# buslamp-r4.net
KiCad netlist of a schematic drawn in EAGLE
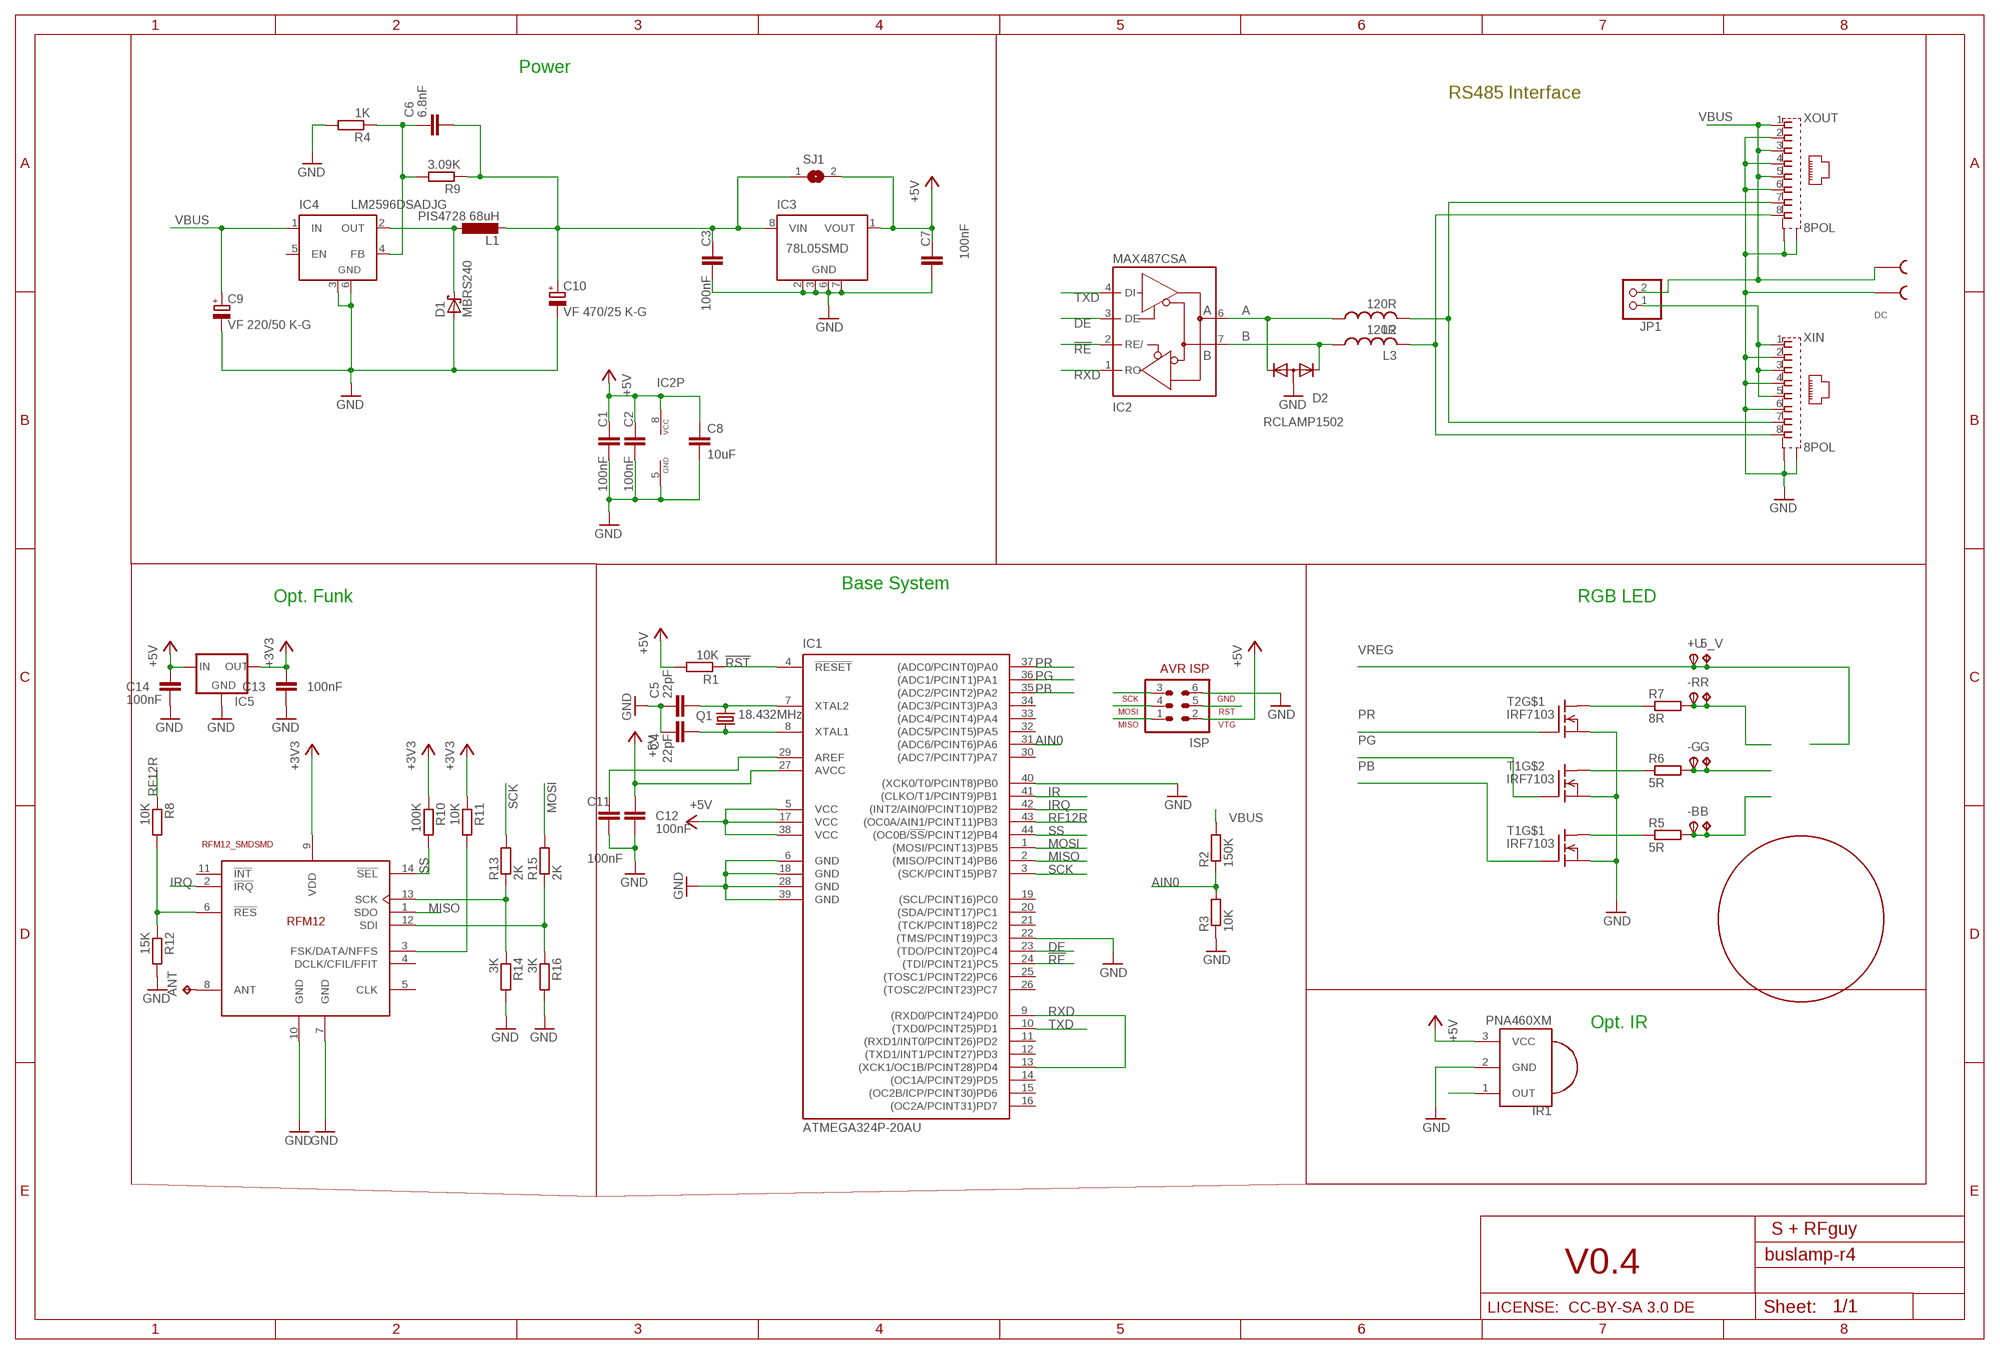
[diagram p0: schematic, sheet 1]

(export (version "E")
  (design (tool "Eeschema 10.0.6"))
  (components
    (comp (ref "+U")
      (value "TPSTP212R")
      (footprint "eagle-import:TP212R")
      (libsource (lib "eagle-import") (part "TPSTP212R"))
    )
    (comp (ref "-B")
      (value "TPSTP212R")
      (footprint "eagle-import:TP212R")
      (libsource (lib "eagle-import") (part "TPSTP212R"))
    )
    (comp (ref "-G")
      (value "TPSTP212R")
      (footprint "eagle-import:TP212R")
      (libsource (lib "eagle-import") (part "TPSTP212R"))
    )
    (comp (ref "-R")
      (value "TPSTP212R")
      (footprint "eagle-import:TP212R")
      (libsource (lib "eagle-import") (part "TPSTP212R"))
    )
    (comp (ref "5_V")
      (value "TPPAD1-13")
      (footprint "eagle-import:P1-13")
      (libsource (lib "eagle-import") (part "TPPAD1-13"))
    )
    (comp (ref "ANT")
      (value "TPPAD1-13")
      (footprint "eagle-import:P1-13")
      (libsource (lib "eagle-import") (part "TPPAD1-13"))
    )
    (comp (ref "B")
      (value "TPPAD1-13")
      (footprint "eagle-import:P1-13")
      (libsource (lib "eagle-import") (part "TPPAD1-13"))
    )
    (comp (ref "C1")
      (value "100nF")
      (footprint "eagle-import:C0805K")
      (libsource (lib "eagle-import") (part "C-EUC0805K"))
    )
    (comp (ref "C2")
      (value "100nF")
      (footprint "eagle-import:C0805K")
      (libsource (lib "eagle-import") (part "C-EUC0805K"))
    )
    (comp (ref "C3")
      (value "100nF")
      (footprint "eagle-import:C0805K")
      (libsource (lib "eagle-import") (part "C-EUC0805K"))
    )
    (comp (ref "C4")
      (value "22pF")
      (footprint "eagle-import:C0805K")
      (libsource (lib "eagle-import") (part "C-EUC0805K"))
    )
    (comp (ref "C5")
      (value "22pF")
      (footprint "eagle-import:C0805K")
      (libsource (lib "eagle-import") (part "C-EUC0805K"))
    )
    (comp (ref "C6")
      (value "6.8nF")
      (footprint "eagle-import:C0805K")
      (libsource (lib "eagle-import") (part "C-EUC0805K"))
    )
    (comp (ref "C7")
      (value "100nF")
      (footprint "eagle-import:C0805K")
      (libsource (lib "eagle-import") (part "C-EUC0805K"))
    )
    (comp (ref "C8")
      (value "10uF")
      (footprint "eagle-import:C1210")
      (libsource (lib "eagle-import") (part "C-EUC1210"))
    )
    (comp (ref "C9")
      (value "VF 220/50 K-G")
      (footprint "eagle-import:UD-10X10_NICHICON")
      (libsource (lib "eagle-import") (part "CPOL-EUUD-10X10"))
    )
    (comp (ref "C10")
      (value "VF 470/25 K-G")
      (footprint "eagle-import:UD-10X10_NICHICON")
      (libsource (lib "eagle-import") (part "CPOL-EUUD-10X10"))
    )
    (comp (ref "C11")
      (value "100nF")
      (footprint "eagle-import:C0805")
      (libsource (lib "eagle-import") (part "C-EUC0805"))
    )
    (comp (ref "C12")
      (value "100nF")
      (footprint "eagle-import:C0805")
      (libsource (lib "eagle-import") (part "C-EUC0805"))
    )
    (comp (ref "C13")
      (value "100nF")
      (footprint "eagle-import:C0805")
      (libsource (lib "eagle-import") (part "C-EUC0805"))
    )
    (comp (ref "C14")
      (value "100nF")
      (footprint "eagle-import:C0805")
      (libsource (lib "eagle-import") (part "C-EUC0805"))
    )
    (comp (ref "D1")
      (value "MBRS240")
      (footprint "eagle-import:SMB")
      (libsource (lib "eagle-import") (part "MBRS130LT3"))
    )
    (comp (ref "D2")
      (value "RCLAMP1502")
      (footprint "eagle-import:SOT23")
      (libsource (lib "eagle-import") (part "DIODE-2CA|ACSOT23"))
    )
    (comp (ref "DC")
      (value "STL-266-2")
      (footprint "eagle-import:STL-266-2")
      (libsource (lib "eagle-import") (part "STL-266-2"))
    )
    (comp (ref "G")
      (value "TPPAD1-13")
      (footprint "eagle-import:P1-13")
      (libsource (lib "eagle-import") (part "TPPAD1-13"))
    )
    (comp (ref "IC1")
      (value "ATMEGA324P-20AU")
      (footprint "eagle-import:TQFP44")
      (libsource (lib "eagle-import") (part "MEGA164P/324P/644P-AU"))
    )
    (comp (ref "IC2")
      (value "MAX487CSA")
      (footprint "eagle-import:SO08")
      (libsource (lib "eagle-import") (part "MAX481CSA"))
    )
    (comp (ref "IC3")
      (value "78L05SMD")
      (footprint "eagle-import:SO08")
      (libsource (lib "eagle-import") (part "78LSMD05"))
    )
    (comp (ref "IC4")
      (value "LM2596DSADJG")
      (footprint "eagle-import:TO263-5")
      (libsource (lib "eagle-import") (part "LM2596S"))
    )
    (comp (ref "IC5")
      (value "MCP1700SOT23")
      (footprint "eagle-import:SOT23")
      (libsource (lib "eagle-import") (part "MCP1700SOT23"))
    )
    (comp (ref "IR1")
      (value "PNA460XM")
      (footprint "eagle-import:PNA460XM")
      (libsource (lib "eagle-import") (part "PNA460XM"))
    )
    (comp (ref "ISP")
      (value "AVR-ISP-6")
      (footprint "eagle-import:AVR-ISP-6")
      (libsource (lib "eagle-import") (part "AVR-ISP-6"))
    )
    (comp (ref "JP1")
      (value "PINHD-1X2")
      (footprint "eagle-import:1X02")
      (libsource (lib "eagle-import") (part "PINHD-1X2"))
    )
    (comp (ref "L1")
      (value "PIS4728 68uH")
      (footprint "eagle-import:PIS4728")
      (libsource (lib "eagle-import") (part "PSI4728"))
    )
    (comp (ref "L2")
      (value "120R")
      (footprint "eagle-import:L0603")
      (libsource (lib "eagle-import") (part "L-USL0603"))
    )
    (comp (ref "L3")
      (value "120R")
      (footprint "eagle-import:L0603")
      (libsource (lib "eagle-import") (part "L-USL0603"))
    )
    (comp (ref "Q1")
      (value "18.432MHz")
      (footprint "eagle-import:HC49_S")
      (libsource (lib "eagle-import") (part "CRYTALHC49S"))
    )
    (comp (ref "R")
      (value "TPPAD1-13")
      (footprint "eagle-import:P1-13")
      (libsource (lib "eagle-import") (part "TPPAD1-13"))
    )
    (comp (ref "R1")
      (value "10K")
      (footprint "eagle-import:M0805")
      (libsource (lib "eagle-import") (part "R-EU_M0805"))
    )
    (comp (ref "R2")
      (value "150K")
      (footprint "eagle-import:R0805")
      (libsource (lib "eagle-import") (part "R-EU_R0805"))
    )
    (comp (ref "R3")
      (value "10K")
      (footprint "eagle-import:R0805")
      (libsource (lib "eagle-import") (part "R-EU_R0805"))
    )
    (comp (ref "R4")
      (value "1K")
      (footprint "eagle-import:M0805")
      (libsource (lib "eagle-import") (part "R-EU_M0805"))
    )
    (comp (ref "R5")
      (value "5R")
      (footprint "eagle-import:0617_17")
      (libsource (lib "eagle-import") (part "rclml_R-EU_0617/17"))
    )
    (comp (ref "R6")
      (value "5R")
      (footprint "eagle-import:0617_17")
      (libsource (lib "eagle-import") (part "rclml_R-EU_0617/17"))
    )
    (comp (ref "R7")
      (value "8R")
      (footprint "eagle-import:0617_17")
      (libsource (lib "eagle-import") (part "rclml_R-EU_0617/17"))
    )
    (comp (ref "R8")
      (value "10K")
      (footprint "eagle-import:M0805")
      (libsource (lib "eagle-import") (part "R-EU_M0805"))
    )
    (comp (ref "R9")
      (value "3.09K")
      (footprint "eagle-import:M0805")
      (libsource (lib "eagle-import") (part "R-EU_M0805"))
    )
    (comp (ref "R10")
      (value "100K")
      (footprint "eagle-import:M0805")
      (libsource (lib "eagle-import") (part "R-EU_M0805"))
    )
    (comp (ref "R11")
      (value "10K")
      (footprint "eagle-import:M0805")
      (libsource (lib "eagle-import") (part "R-EU_M0805"))
    )
    (comp (ref "R12")
      (value "15K")
      (footprint "eagle-import:M0805")
      (libsource (lib "eagle-import") (part "R-EU_M0805"))
    )
    (comp (ref "R13")
      (value "2K")
      (footprint "eagle-import:M0805")
      (libsource (lib "eagle-import") (part "R-EU_M0805"))
    )
    (comp (ref "R14")
      (value "3K")
      (footprint "eagle-import:M0805")
      (libsource (lib "eagle-import") (part "R-EU_M0805"))
    )
    (comp (ref "R15")
      (value "2K")
      (footprint "eagle-import:M0805")
      (libsource (lib "eagle-import") (part "R-EU_M0805"))
    )
    (comp (ref "R16")
      (value "3K")
      (footprint "eagle-import:M0805")
      (libsource (lib "eagle-import") (part "R-EU_M0805"))
    )
    (comp (ref "RF1")
      (value "RFM12_SMDSMD")
      (footprint "eagle-import:RFM12")
      (libsource (lib "eagle-import") (part "RFM12_SMDSMD"))
    )
    (comp (ref "SJ1") (value "SJ") (footprint "eagle-import:SJ") (libsource (lib "eagle-import") (part "SJ")))
    (comp (ref "T1")
      (value "IRF7103")
      (footprint "eagle-import:SO-8")
      (libsource (lib "eagle-import") (part "IRF7103"))
    )
    (comp (ref "T2")
      (value "IRF7103")
      (footprint "eagle-import:SO-8")
      (libsource (lib "eagle-import") (part "IRF7103"))
    )
    (comp (ref "U$2")
      (value "KK-STERN")
      (footprint "eagle-import:STERN")
      (libsource (lib "eagle-import") (part "KK-STERN"))
    )
    (comp (ref "XIN")
      (value "8POL")
      (footprint "eagle-import:8POL")
      (libsource (lib "eagle-import") (part "8POL"))
    )
    (comp (ref "XOUT")
      (value "8POL")
      (footprint "eagle-import:8POL")
      (libsource (lib "eagle-import") (part "8POL"))
    )
  )
  (nets
    (net (code "1") (name "+3V3") (class "Default")
      (node (ref "C13") (pin "2") (pinfunction "2_2") (pintype "passive"))
      (node (ref "IC5") (pin "2") (pinfunction "OUT_2") (pintype "passive"))
      (node (ref "R10") (pin "1") (pinfunction "1_1") (pintype "passive"))
      (node (ref "R11") (pin "1") (pinfunction "1_1") (pintype "passive"))
      (node (ref "RF1") (pin "9") (pinfunction "VDD_9") (pintype "power_in"))
    )
    (net (code "2") (name "+5V") (class "Default")
      (node (ref "C1") (pin "1") (pinfunction "1_1") (pintype "passive"))
      (node (ref "C12") (pin "2") (pinfunction "2_2") (pintype "passive"))
      (node (ref "C14") (pin "2") (pinfunction "2_2") (pintype "passive"))
      (node (ref "C2") (pin "1") (pinfunction "1_1") (pintype "passive"))
      (node (ref "C7") (pin "1") (pinfunction "1_1") (pintype "passive"))
      (node (ref "C8") (pin "1") (pinfunction "1_1") (pintype "passive"))
      (node (ref "IC1") (pin "17") (pinfunction "VCC_17") (pintype "power_in"))
      (node (ref "IC1") (pin "27") (pinfunction "AVCC_27") (pintype "power_in"))
      (node (ref "IC1") (pin "38") (pinfunction "VCC_38") (pintype "power_in"))
      (node (ref "IC1") (pin "5") (pinfunction "VCC_5") (pintype "power_in"))
      (node (ref "IC2") (pin "8") (pinfunction "VCC_8") (pintype "power_in"))
      (node (ref "IC3") (pin "1") (pinfunction "VOUT_1") (pintype "output"))
      (node (ref "IC5") (pin "3") (pinfunction "IN_3") (pintype "input"))
      (node (ref "IR1") (pin "3") (pinfunction "VCC_3") (pintype "power_in"))
      (node (ref "ISP") (pin "2") (pinfunction "2_2") (pintype "passive"))
      (node (ref "R1") (pin "2") (pinfunction "2_2") (pintype "passive"))
      (node (ref "SJ1") (pin "2") (pinfunction "2_2") (pintype "passive"))
    )
    (net (code "3") (name "/A") (class "Default")
      (node (ref "L2") (pin "2") (pinfunction "2_2") (pintype "passive"))
      (node (ref "XIN") (pin "7") (pinfunction "7_7") (pintype "passive"))
      (node (ref "XOUT") (pin "7") (pinfunction "7_7") (pintype "passive"))
    )
    (net (code "4") (name "/AIN0") (class "Default")
      (node (ref "IC1") (pin "31") (pinfunction "(ADC6/PCINT6)PA6_31") (pintype "bidirectional"))
      (node (ref "R2") (pin "1") (pinfunction "1_1") (pintype "passive"))
      (node (ref "R3") (pin "2") (pinfunction "2_2") (pintype "passive"))
    )
    (net (code "5") (name "/B") (class "Default")
      (node (ref "L3") (pin "2") (pinfunction "2_2") (pintype "passive"))
      (node (ref "XIN") (pin "8") (pinfunction "8_8") (pintype "passive"))
      (node (ref "XOUT") (pin "8") (pinfunction "8_8") (pintype "passive"))
    )
    (net (code "6") (name "/DE") (class "Default")
      (node (ref "IC1") (pin "23") (pinfunction "(TDO/PCINT20)PC4_23") (pintype "bidirectional"))
      (node (ref "IC2") (pin "3") (pinfunction "DE_3") (pintype "input"))
    )
    (net (code "7") (name "/IR") (class "Default")
      (node (ref "IC1") (pin "41") (pinfunction "(CLKO/T1/PCINT9)PB1_41") (pintype "bidirectional"))
      (node (ref "IR1") (pin "1") (pinfunction "OUT_1") (pintype "output"))
    )
    (net (code "8") (name "/IRQ") (class "Default")
      (node (ref "IC1") (pin "42") (pinfunction "(INT2/AIN0/PCINT10)PB2_42") (pintype "bidirectional"))
      (node (ref "RF1") (pin "2") (pinfunction "~{IRQ}_2") (pintype "output"))
    )
    (net (code "9") (name "/MISO") (class "Default")
      (node (ref "IC1") (pin "2") (pinfunction "(MISO/PCINT14)PB6_2") (pintype "bidirectional"))
      (node (ref "ISP") (pin "1") (pinfunction "1_1") (pintype "passive"))
      (node (ref "RF1") (pin "1") (pinfunction "SDO_1") (pintype "output"))
    )
    (net (code "10") (name "/MOSI") (class "Default")
      (node (ref "IC1") (pin "1") (pinfunction "(MOSI/PCINT13)PB5_1") (pintype "bidirectional"))
      (node (ref "ISP") (pin "4") (pinfunction "4_4") (pintype "passive"))
      (node (ref "R15") (pin "2") (pinfunction "2_2") (pintype "passive"))
    )
    (net (code "11") (name "/PB") (class "Default")
      (node (ref "IC1") (pin "35") (pinfunction "(ADC2/PCINT2)PA2_35") (pintype "bidirectional"))
      (node (ref "T1") (pin "2") (pinfunction "G_2") (pintype "passive"))
    )
    (net (code "12") (name "/PG") (class "Default")
      (node (ref "IC1") (pin "36") (pinfunction "(ADC1/PCINT1)PA1_36") (pintype "bidirectional"))
      (node (ref "T1") (pin "4") (pinfunction "G_4") (pintype "passive"))
    )
    (net (code "13") (name "/PR") (class "Default")
      (node (ref "IC1") (pin "37") (pinfunction "(ADC0/PCINT0)PA0_37") (pintype "bidirectional"))
      (node (ref "T2") (pin "2") (pinfunction "G_2") (pintype "passive"))
    )
    (net (code "14") (name "/RF12R") (class "Default")
      (node (ref "IC1") (pin "43") (pinfunction "(OC0A/AIN1/PCINT11)PB3_43") (pintype "bidirectional"))
      (node (ref "R8") (pin "1") (pinfunction "1_1") (pintype "passive"))
    )
    (net (code "15") (name "/RXD") (class "Default")
      (node (ref "IC1") (pin "13") (pinfunction "(XCK1/OC1B/PCINT28)PD4_13") (pintype "bidirectional"))
      (node (ref "IC1") (pin "9") (pinfunction "(RXD0/PCINT24)PD0_9") (pintype "bidirectional"))
      (node (ref "IC2") (pin "1") (pinfunction "RO_1") (pintype "output"))
    )
    (net (code "16") (name "/SCK") (class "Default")
      (node (ref "IC1") (pin "3") (pinfunction "(SCK/PCINT15)PB7_3") (pintype "bidirectional"))
      (node (ref "ISP") (pin "3") (pinfunction "3_3") (pintype "passive"))
      (node (ref "R13") (pin "2") (pinfunction "2_2") (pintype "passive"))
    )
    (net (code "17") (name "/SS") (class "Default")
      (node (ref "IC1") (pin "44") (pinfunction "(OC0B/~{SS}/PCINT12)PB4_44") (pintype "bidirectional"))
      (node (ref "R10") (pin "2") (pinfunction "2_2") (pintype "passive"))
      (node (ref "RF1") (pin "14") (pinfunction "~{SEL}_14") (pintype "input"))
    )
    (net (code "18") (name "/TXD") (class "Default")
      (node (ref "IC1") (pin "10") (pinfunction "(TXD0/PCINT25)PD1_10") (pintype "bidirectional"))
      (node (ref "IC2") (pin "4") (pinfunction "DI_4") (pintype "input"))
    )
    (net (code "19") (name "/VBUS") (class "Default")
      (node (ref "C9") (pin "+") (pinfunction "+_+") (pintype "passive"))
      (node (ref "DC") (pin "P$4") (pinfunction "P$2_P$4") (pintype "bidirectional"))
      (node (ref "IC4") (pin "1") (pinfunction "IN_1") (pintype "input"))
      (node (ref "JP1") (pin "2") (pinfunction "2_2") (pintype "passive"))
      (node (ref "R2") (pin "2") (pinfunction "2_2") (pintype "passive"))
      (node (ref "XOUT") (pin "1") (pinfunction "1_1") (pintype "passive"))
      (node (ref "XOUT") (pin "3") (pinfunction "3_3") (pintype "passive"))
      (node (ref "XOUT") (pin "5") (pinfunction "5_5") (pintype "passive"))
    )
    (net (code "20") (name "/VREG") (class "Default")
      (node (ref "+U") (pin "TP") (pinfunction "PP_TP") (pintype "input"))
      (node (ref "5_V") (pin "TP") (pinfunction "TP_TP") (pintype "input"))
      (node (ref "C10") (pin "+") (pinfunction "+_+") (pintype "passive"))
      (node (ref "C3") (pin "1") (pinfunction "1_1") (pintype "passive"))
      (node (ref "C6") (pin "2") (pinfunction "2_2") (pintype "passive"))
      (node (ref "IC3") (pin "8") (pinfunction "VIN_8") (pintype "passive"))
      (node (ref "L1") (pin "2") (pinfunction "2_2") (pintype "passive"))
      (node (ref "R9") (pin "1") (pinfunction "1_1") (pintype "passive"))
      (node (ref "SJ1") (pin "1") (pinfunction "1_1") (pintype "passive"))
    )
    (net (code "21") (name "/~{RE}") (class "Default")
      (node (ref "IC1") (pin "24") (pinfunction "(TDI/PCINT21)PC5_24") (pintype "bidirectional"))
      (node (ref "IC2") (pin "2") (pinfunction "RE/_2") (pintype "input"))
    )
    (net (code "22") (name "/~{RST}") (class "Default")
      (node (ref "IC1") (pin "4") (pinfunction "~{RESET}_4") (pintype "input"))
      (node (ref "ISP") (pin "5") (pinfunction "5_5") (pintype "passive"))
      (node (ref "R1") (pin "1") (pinfunction "1_1") (pintype "passive"))
    )
    (net (code "23") (name "GND") (class "Default")
      (node (ref "C1") (pin "2") (pinfunction "2_2") (pintype "passive"))
      (node (ref "C10") (pin "-") (pinfunction "-_-") (pintype "passive"))
      (node (ref "C11") (pin "1") (pinfunction "1_1") (pintype "passive"))
      (node (ref "C12") (pin "1") (pinfunction "1_1") (pintype "passive"))
      (node (ref "C13") (pin "1") (pinfunction "1_1") (pintype "passive"))
      (node (ref "C14") (pin "1") (pinfunction "1_1") (pintype "passive"))
      (node (ref "C2") (pin "2") (pinfunction "2_2") (pintype "passive"))
      (node (ref "C3") (pin "2") (pinfunction "2_2") (pintype "passive"))
      (node (ref "C4") (pin "1") (pinfunction "1_1") (pintype "passive"))
      (node (ref "C5") (pin "1") (pinfunction "1_1") (pintype "passive"))
      (node (ref "C7") (pin "2") (pinfunction "2_2") (pintype "passive"))
      (node (ref "C8") (pin "2") (pinfunction "2_2") (pintype "passive"))
      (node (ref "C9") (pin "-") (pinfunction "-_-") (pintype "passive"))
      (node (ref "D1") (pin "A") (pinfunction "A_A") (pintype "passive"))
      (node (ref "D2") (pin "3") (pinfunction "A_3") (pintype "passive"))
      (node (ref "DC") (pin "P$3") (pinfunction "P$1_P$3") (pintype "bidirectional"))
      (node (ref "IC1") (pin "18") (pinfunction "GND_18") (pintype "power_in"))
      (node (ref "IC1") (pin "22") (pinfunction "(TMS/PCINT19)PC3_22") (pintype "bidirectional"))
      (node (ref "IC1") (pin "28") (pinfunction "GND_28") (pintype "power_in"))
      (node (ref "IC1") (pin "39") (pinfunction "GND_39") (pintype "power_in"))
      (node (ref "IC1") (pin "40") (pinfunction "(XCK0/T0/PCINT8)PB0_40") (pintype "bidirectional"))
      (node (ref "IC1") (pin "6") (pinfunction "GND_6") (pintype "power_in"))
      (node (ref "IC2") (pin "5") (pinfunction "GND_5") (pintype "power_in"))
      (node (ref "IC3") (pin "2") (pinfunction "GND_2") (pintype "power_in"))
      (node (ref "IC3") (pin "3") (pinfunction "GND_3") (pintype "power_in"))
      (node (ref "IC3") (pin "6") (pinfunction "GND_6") (pintype "power_in"))
      (node (ref "IC3") (pin "7") (pinfunction "GND_7") (pintype "power_in"))
      (node (ref "IC4") (pin "3") (pinfunction "GND_3") (pintype "power_in"))
      (node (ref "IC4") (pin "6") (pinfunction "GND_6") (pintype "power_in"))
      (node (ref "IC5") (pin "1") (pinfunction "GND_1") (pintype "input"))
      (node (ref "IR1") (pin "2") (pinfunction "GND_2") (pintype "power_in"))
      (node (ref "ISP") (pin "6") (pinfunction "6_6") (pintype "passive"))
      (node (ref "R12") (pin "2") (pinfunction "2_2") (pintype "passive"))
      (node (ref "R14") (pin "2") (pinfunction "2_2") (pintype "passive"))
      (node (ref "R16") (pin "2") (pinfunction "2_2") (pintype "passive"))
      (node (ref "R3") (pin "1") (pinfunction "1_1") (pintype "passive"))
      (node (ref "R4") (pin "2") (pinfunction "2_2") (pintype "passive"))
      (node (ref "RF1") (pin "10") (pinfunction "GND_10") (pintype "passive"))
      (node (ref "RF1") (pin "7") (pinfunction "GND_7") (pintype "passive"))
      (node (ref "T1") (pin "1") (pinfunction "S_1") (pintype "passive"))
      (node (ref "T1") (pin "3") (pinfunction "S_3") (pintype "passive"))
      (node (ref "T2") (pin "1") (pinfunction "S_1") (pintype "passive"))
      (node (ref "XIN") (pin "2") (pinfunction "2_2") (pintype "passive"))
      (node (ref "XIN") (pin "4") (pinfunction "4_4") (pintype "passive"))
      (node (ref "XIN") (pin "6") (pinfunction "6_6") (pintype "passive"))
      (node (ref "XIN") (pin "S1") (pinfunction "S1_S1") (pintype "passive"))
      (node (ref "XIN") (pin "S2") (pinfunction "S2_S2") (pintype "passive"))
      (node (ref "XOUT") (pin "2") (pinfunction "2_2") (pintype "passive"))
      (node (ref "XOUT") (pin "4") (pinfunction "4_4") (pintype "passive"))
      (node (ref "XOUT") (pin "6") (pinfunction "6_6") (pintype "passive"))
      (node (ref "XOUT") (pin "S1") (pinfunction "S1_S1") (pintype "passive"))
      (node (ref "XOUT") (pin "S2") (pinfunction "S2_S2") (pintype "passive"))
    )
    (net (code "24") (name "Net-(-B-PP)") (class "Default")
      (node (ref "-B") (pin "TP") (pinfunction "PP_TP") (pintype "input"))
      (node (ref "B") (pin "TP") (pinfunction "TP_TP") (pintype "input"))
      (node (ref "R5") (pin "2") (pinfunction "2_2") (pintype "passive"))
    )
    (net (code "25") (name "Net-(-G-PP)") (class "Default")
      (node (ref "-G") (pin "TP") (pinfunction "PP_TP") (pintype "input"))
      (node (ref "G") (pin "TP") (pinfunction "TP_TP") (pintype "input"))
      (node (ref "R6") (pin "2") (pinfunction "2_2") (pintype "passive"))
    )
    (net (code "26") (name "Net-(-R-PP)") (class "Default")
      (node (ref "-R") (pin "TP") (pinfunction "PP_TP") (pintype "input"))
      (node (ref "R") (pin "TP") (pinfunction "TP_TP") (pintype "input"))
      (node (ref "R7") (pin "2") (pinfunction "2_2") (pintype "passive"))
    )
    (net (code "27") (name "Net-(D2-K1)") (class "Default")
      (node (ref "D2") (pin "1") (pinfunction "K1_1") (pintype "passive"))
      (node (ref "IC2") (pin "7") (pinfunction "B_7") (pintype "passive"))
      (node (ref "L3") (pin "1") (pinfunction "1_1") (pintype "passive"))
    )
    (net (code "28") (name "Net-(D2-K2)") (class "Default")
      (node (ref "D2") (pin "2") (pinfunction "K2_2") (pintype "passive"))
      (node (ref "IC2") (pin "6") (pinfunction "A_6") (pintype "passive"))
      (node (ref "L2") (pin "1") (pinfunction "1_1") (pintype "passive"))
    )
    (net (code "29") (name "Net-(IC1-AREF)") (class "Default")
      (node (ref "C11") (pin "2") (pinfunction "2_2") (pintype "passive"))
      (node (ref "IC1") (pin "29") (pinfunction "AREF_29") (pintype "power_in"))
    )
    (net (code "30") (name "Net-(IC1-XTAL1)") (class "Default")
      (node (ref "C4") (pin "2") (pinfunction "2_2") (pintype "passive"))
      (node (ref "IC1") (pin "8") (pinfunction "XTAL1_8") (pintype "input"))
      (node (ref "Q1") (pin "1") (pinfunction "1_1") (pintype "passive"))
    )
    (net (code "31") (name "Net-(IC1-XTAL2)") (class "Default")
      (node (ref "C5") (pin "2") (pinfunction "2_2") (pintype "passive"))
      (node (ref "IC1") (pin "7") (pinfunction "XTAL2_7") (pintype "output"))
      (node (ref "Q1") (pin "2") (pinfunction "2_2") (pintype "passive"))
    )
    (net (code "32") (name "Net-(IC4-FB)") (class "Default")
      (node (ref "C6") (pin "1") (pinfunction "1_1") (pintype "passive"))
      (node (ref "IC4") (pin "4") (pinfunction "FB_4") (pintype "input"))
      (node (ref "R4") (pin "1") (pinfunction "1_1") (pintype "passive"))
      (node (ref "R9") (pin "2") (pinfunction "2_2") (pintype "passive"))
    )
    (net (code "33") (name "Net-(IC4-OUT)") (class "Default")
      (node (ref "D1") (pin "C") (pinfunction "C_C") (pintype "passive"))
      (node (ref "IC4") (pin "2") (pinfunction "OUT_2") (pintype "output"))
      (node (ref "L1") (pin "1") (pinfunction "1_1") (pintype "passive"))
    )
    (net (code "34") (name "Net-(JP1-Pad1)") (class "Default")
      (node (ref "JP1") (pin "1") (pinfunction "1_1") (pintype "passive"))
      (node (ref "XIN") (pin "1") (pinfunction "1_1") (pintype "passive"))
      (node (ref "XIN") (pin "3") (pinfunction "3_3") (pintype "passive"))
      (node (ref "XIN") (pin "5") (pinfunction "5_5") (pintype "passive"))
    )
    (net (code "35") (name "Net-(RF1-ANT)") (class "Default")
      (node (ref "ANT") (pin "TP") (pinfunction "TP_TP") (pintype "input"))
      (node (ref "RF1") (pin "8") (pinfunction "ANT_8") (pintype "bidirectional"))
    )
    (net (code "36") (name "Net-(RF1-FSK{slash}DATA{slash}NFFS)") (class "Default")
      (node (ref "R11") (pin "2") (pinfunction "2_2") (pintype "passive"))
      (node (ref "RF1") (pin "3") (pinfunction "FSK/DATA/NFFS_3") (pintype "bidirectional"))
    )
    (net (code "37") (name "Net-(RF1-SCK)") (class "Default")
      (node (ref "R13") (pin "1") (pinfunction "1_1") (pintype "passive"))
      (node (ref "R14") (pin "1") (pinfunction "1_1") (pintype "passive"))
      (node (ref "RF1") (pin "13") (pinfunction "SCK_13") (pintype "input"))
    )
    (net (code "38") (name "Net-(RF1-SDI)") (class "Default")
      (node (ref "R15") (pin "1") (pinfunction "1_1") (pintype "passive"))
      (node (ref "R16") (pin "1") (pinfunction "1_1") (pintype "passive"))
      (node (ref "RF1") (pin "12") (pinfunction "SDI_12") (pintype "input"))
    )
    (net (code "39") (name "Net-(RF1-~{RES})") (class "Default")
      (node (ref "R12") (pin "1") (pinfunction "1_1") (pintype "passive"))
      (node (ref "R8") (pin "2") (pinfunction "2_2") (pintype "passive"))
      (node (ref "RF1") (pin "6") (pinfunction "~{RES}_6") (pintype "bidirectional"))
    )
    (net (code "40") (name "Net-(T1A-D1)") (class "Default")
      (node (ref "R5") (pin "1") (pinfunction "1_1") (pintype "passive"))
      (node (ref "T1") (pin "8") (pinfunction "D1_8") (pintype "passive"))
    )
    (net (code "41") (name "Net-(T1B-D1)") (class "Default")
      (node (ref "R6") (pin "1") (pinfunction "1_1") (pintype "passive"))
      (node (ref "T1") (pin "5") (pinfunction "D1_5") (pintype "passive"))
    )
    (net (code "42") (name "Net-(T2A-D1)") (class "Default")
      (node (ref "R7") (pin "1") (pinfunction "1_1") (pintype "passive"))
      (node (ref "T2") (pin "8") (pinfunction "D1_8") (pintype "passive"))
    )
    (net (code "43") (name "unconnected-(IC1-(ADC3{slash}PCINT3)PA3-Pad34)") (class "Default")
      (node (ref "IC1") (pin "34") (pinfunction "(ADC3/PCINT3)PA3_34") (pintype "bidirectional"))
    )
    (net (code "44") (name "unconnected-(IC1-(ADC4{slash}PCINT4)PA4-Pad33)") (class "Default")
      (node (ref "IC1") (pin "33") (pinfunction "(ADC4/PCINT4)PA4_33") (pintype "bidirectional"))
    )
    (net (code "45") (name "unconnected-(IC1-(ADC5{slash}PCINT5)PA5-Pad32)") (class "Default")
      (node (ref "IC1") (pin "32") (pinfunction "(ADC5/PCINT5)PA5_32") (pintype "bidirectional"))
    )
    (net (code "46") (name "unconnected-(IC1-(ADC7{slash}PCINT7)PA7-Pad30)") (class "Default")
      (node (ref "IC1") (pin "30") (pinfunction "(ADC7/PCINT7)PA7_30") (pintype "bidirectional"))
    )
    (net (code "47") (name "unconnected-(IC1-(OC1A{slash}PCINT29)PD5-Pad14)") (class "Default")
      (node (ref "IC1") (pin "14") (pinfunction "(OC1A/PCINT29)PD5_14") (pintype "bidirectional"))
    )
    (net (code "48") (name "unconnected-(IC1-(OC2A{slash}PCINT31)PD7-Pad16)") (class "Default")
      (node (ref "IC1") (pin "16") (pinfunction "(OC2A/PCINT31)PD7_16") (pintype "bidirectional"))
    )
    (net (code "49") (name "unconnected-(IC1-(OC2B{slash}ICP{slash}PCINT30)PD6-Pad15)") (class "Default")
      (node (ref "IC1") (pin "15") (pinfunction "(OC2B/ICP/PCINT30)PD6_15") (pintype "bidirectional"))
    )
    (net (code "50") (name "unconnected-(IC1-(RXD1{slash}INT0{slash}PCINT26)PD2-Pad11)") (class "Default")
      (node (ref "IC1") (pin "11") (pinfunction "(RXD1/INT0/PCINT26)PD2_11") (pintype "bidirectional"))
    )
    (net (code "51") (name "unconnected-(IC1-(SCL{slash}PCINT16)PC0-Pad19)") (class "Default")
      (node (ref "IC1") (pin "19") (pinfunction "(SCL/PCINT16)PC0_19") (pintype "bidirectional"))
    )
    (net (code "52") (name "unconnected-(IC1-(SDA{slash}PCINT17)PC1-Pad20)") (class "Default")
      (node (ref "IC1") (pin "20") (pinfunction "(SDA/PCINT17)PC1_20") (pintype "bidirectional"))
    )
    (net (code "53") (name "unconnected-(IC1-(TCK{slash}PCINT18)PC2-Pad21)") (class "Default")
      (node (ref "IC1") (pin "21") (pinfunction "(TCK/PCINT18)PC2_21") (pintype "bidirectional"))
    )
    (net (code "54") (name "unconnected-(IC1-(TOSC1{slash}PCINT22)PC6-Pad25)") (class "Default")
      (node (ref "IC1") (pin "25") (pinfunction "(TOSC1/PCINT22)PC6_25") (pintype "bidirectional"))
    )
    (net (code "55") (name "unconnected-(IC1-(TOSC2{slash}PCINT23)PC7-Pad26)") (class "Default")
      (node (ref "IC1") (pin "26") (pinfunction "(TOSC2/PCINT23)PC7_26") (pintype "bidirectional"))
    )
    (net (code "56") (name "unconnected-(IC1-(TXD1{slash}INT1{slash}PCINT27)PD3-Pad12)") (class "Default")
      (node (ref "IC1") (pin "12") (pinfunction "(TXD1/INT1/PCINT27)PD3_12") (pintype "bidirectional"))
    )
    (net (code "57") (name "unconnected-(IC4-EN-Pad5)") (class "Default")
      (node (ref "IC4") (pin "5") (pinfunction "EN_5") (pintype "input"))
    )
    (net (code "58") (name "unconnected-(RF1-CLK-Pad5)") (class "Default")
      (node (ref "RF1") (pin "5") (pinfunction "CLK_5") (pintype "output"))
    )
    (net (code "59") (name "unconnected-(RF1-DCLK{slash}CFIL{slash}FFIT-Pad4)") (class "Default")
      (node (ref "RF1") (pin "4") (pinfunction "DCLK/CFIL/FFIT_4") (pintype "bidirectional"))
    )
    (net (code "60") (name "unconnected-(RF1-~{INT}-Pad11)") (class "Default")
      (node (ref "RF1") (pin "11") (pinfunction "~{INT}_11") (pintype "bidirectional"))
    )
    (net (code "61") (name "unconnected-(T1A-D-Pad7)") (class "Default")
      (node (ref "T1") (pin "7") (pinfunction "D_7") (pintype "passive"))
    )
    (net (code "62") (name "unconnected-(T1B-D-Pad6)") (class "Default")
      (node (ref "T1") (pin "6") (pinfunction "D_6") (pintype "passive"))
    )
    (net (code "63") (name "unconnected-(T2A-D-Pad7)") (class "Default")
      (node (ref "T2") (pin "7") (pinfunction "D_7") (pintype "passive"))
    )
  )
)
